# headers.net
KiCad netlist of a schematic drawn in EAGLE
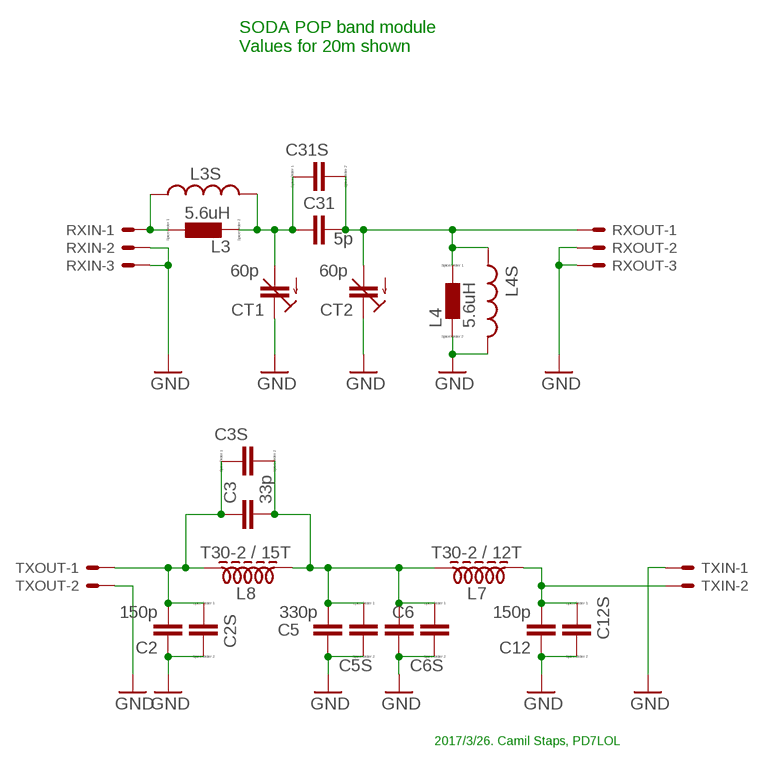
[diagram p0: schematic, sheet 1]

(export (version "E")
  (design (tool "Eeschema 10.0.6"))
  (components
    (comp (ref "C2")
      (value "150p")
      (footprint "eagle-import:C5B2.5")
      (libsource (lib "eagle-import") (part "C5/2.5"))
    )
    (comp (ref "C2S")
      (value "CC0603")
      (footprint "eagle-import:C0603")
      (libsource (lib "eagle-import") (part "CC0603"))
    )
    (comp (ref "C3")
      (value "33p")
      (footprint "eagle-import:C5B2.5")
      (libsource (lib "eagle-import") (part "C5/2.5"))
    )
    (comp (ref "C3S")
      (value "CC0603")
      (footprint "eagle-import:C0603")
      (libsource (lib "eagle-import") (part "CC0603"))
    )
    (comp (ref "C5")
      (value "330p")
      (footprint "eagle-import:C5B2.5")
      (libsource (lib "eagle-import") (part "C5/2.5"))
    )
    (comp (ref "C5S")
      (value "CC0603")
      (footprint "eagle-import:C0603")
      (libsource (lib "eagle-import") (part "CC0603"))
    )
    (comp (ref "C6")
      (value "330p")
      (footprint "eagle-import:C5B2.5")
      (libsource (lib "eagle-import") (part "C5/2.5"))
    )
    (comp (ref "C6S")
      (value "CC0603")
      (footprint "eagle-import:C0603")
      (libsource (lib "eagle-import") (part "CC0603"))
    )
    (comp (ref "C12")
      (value "150p")
      (footprint "eagle-import:C5B2.5")
      (libsource (lib "eagle-import") (part "C5/2.5"))
    )
    (comp (ref "C12S")
      (value "CC0603")
      (footprint "eagle-import:C0603")
      (libsource (lib "eagle-import") (part "CC0603"))
    )
    (comp (ref "C31")
      (value "5p")
      (footprint "eagle-import:C5B2.5")
      (libsource (lib "eagle-import") (part "C5/2.5"))
    )
    (comp (ref "C31S")
      (value "CC0603")
      (footprint "eagle-import:C0603")
      (libsource (lib "eagle-import") (part "CC0603"))
    )
    (comp (ref "CT1")
      (value "60p")
      (footprint "eagle-import:CTRIMTZ03")
      (libsource (lib "eagle-import") (part "C-TRIMMTZ03"))
    )
    (comp (ref "CT2")
      (value "60p")
      (footprint "eagle-import:CTRIMTZ03")
      (libsource (lib "eagle-import") (part "C-TRIMMTZ03"))
    )
    (comp (ref "L3")
      (value "5.6uH")
      (footprint "eagle-import:0207_10")
      (libsource (lib "eagle-import") (part "L0207/10"))
    )
    (comp (ref "L3S")
      (value "L-USL2012C")
      (footprint "eagle-import:L2012C")
      (libsource (lib "eagle-import") (part "L-USL2012C"))
    )
    (comp (ref "L4")
      (value "5.6uH")
      (footprint "eagle-import:0207_10")
      (libsource (lib "eagle-import") (part "L0207/10"))
    )
    (comp (ref "L4S")
      (value "L-USL2012C")
      (footprint "eagle-import:L2012C")
      (libsource (lib "eagle-import") (part "L-USL2012C"))
    )
    (comp (ref "L7")
      (value "T30-2 / 12T")
      (footprint "eagle-import:T30-2-28AWG-15T")
      (libsource (lib "eagle-import") (part "INDUCTORT30-2-28AWG-15T"))
    )
    (comp (ref "L8")
      (value "T30-2 / 15T")
      (footprint "eagle-import:T30-2-28AWG-15T")
      (libsource (lib "eagle-import") (part "INDUCTORT30-2-28AWG-15T"))
    )
    (comp (ref "RXIN")
      (value "22-23-2031")
      (footprint "eagle-import:22-23-2031")
      (fields (field (name "MF") "MOLEX"))
      (libsource (lib "eagle-import") (part "22-23-2031"))
    )
    (comp (ref "RXOUT")
      (value "22-23-2031")
      (footprint "eagle-import:22-23-2031")
      (fields (field (name "MF") "MOLEX"))
      (libsource (lib "eagle-import") (part "22-23-2031"))
    )
    (comp (ref "TXIN")
      (value "22-23-2021")
      (footprint "eagle-import:22-23-2021")
      (fields (field (name "MF") "MOLEX"))
      (libsource (lib "eagle-import") (part "22-23-2021"))
    )
    (comp (ref "TXOUT")
      (value "22-23-2021")
      (footprint "eagle-import:22-23-2021")
      (fields (field (name "MF") "MOLEX"))
      (libsource (lib "eagle-import") (part "22-23-2021"))
    )
  )
  (nets
    (net (code "1") (name "GND") (class "Default")
      (node (ref "C12") (pin "1") (pinfunction "1_1") (pintype "passive"))
      (node (ref "C12S") (pin "2") (pinfunction "2_2") (pintype "passive"))
      (node (ref "C2") (pin "1") (pinfunction "1_1") (pintype "passive"))
      (node (ref "C2S") (pin "2") (pinfunction "2_2") (pintype "passive"))
      (node (ref "C5") (pin "1") (pinfunction "1_1") (pintype "passive"))
      (node (ref "C5S") (pin "2") (pinfunction "2_2") (pintype "passive"))
      (node (ref "C6") (pin "1") (pinfunction "1_1") (pintype "passive"))
      (node (ref "C6S") (pin "2") (pinfunction "2_2") (pintype "passive"))
      (node (ref "CT1") (pin "1") (pinfunction "E_1") (pintype "passive"))
      (node (ref "CT2") (pin "1") (pinfunction "E_1") (pintype "passive"))
      (node (ref "L4") (pin "2") (pinfunction "2_2") (pintype "passive"))
      (node (ref "L4S") (pin "2") (pinfunction "2_2") (pintype "passive"))
      (node (ref "RXIN") (pin "2") (pinfunction "S_2") (pintype "passive"))
      (node (ref "RXIN") (pin "3") (pinfunction "S_3") (pintype "passive"))
      (node (ref "RXOUT") (pin "2") (pinfunction "S_2") (pintype "passive"))
      (node (ref "RXOUT") (pin "3") (pinfunction "S_3") (pintype "passive"))
      (node (ref "TXIN") (pin "1") (pinfunction "S_1") (pintype "passive"))
      (node (ref "TXOUT") (pin "2") (pinfunction "S_2") (pintype "passive"))
    )
    (net (code "2") (name "Net-(CT1-A)") (class "Default")
      (node (ref "C31") (pin "1") (pinfunction "1_1") (pintype "passive"))
      (node (ref "C31S") (pin "1") (pinfunction "1_1") (pintype "passive"))
      (node (ref "CT1") (pin "2") (pinfunction "A_2") (pintype "passive"))
      (node (ref "L3") (pin "2") (pinfunction "2_2") (pintype "passive"))
      (node (ref "L3S") (pin "2") (pinfunction "2_2") (pintype "passive"))
    )
    (net (code "3") (name "Net-(CT2-A)") (class "Default")
      (node (ref "C31") (pin "2") (pinfunction "2_2") (pintype "passive"))
      (node (ref "C31S") (pin "2") (pinfunction "2_2") (pintype "passive"))
      (node (ref "CT2") (pin "2") (pinfunction "A_2") (pintype "passive"))
      (node (ref "L4") (pin "1") (pinfunction "1_1") (pintype "passive"))
      (node (ref "L4S") (pin "1") (pinfunction "1_1") (pintype "passive"))
      (node (ref "RXOUT") (pin "1") (pinfunction "S_1") (pintype "passive"))
    )
    (net (code "4") (name "Net-(L7-1)") (class "Default")
      (node (ref "C12") (pin "2") (pinfunction "2_2") (pintype "passive"))
      (node (ref "C12S") (pin "1") (pinfunction "1_1") (pintype "passive"))
      (node (ref "L7") (pin "P$1") (pinfunction "1_P$1") (pintype "passive"))
      (node (ref "TXIN") (pin "2") (pinfunction "S_2") (pintype "passive"))
    )
    (net (code "5") (name "Net-(L7-2)") (class "Default")
      (node (ref "C3") (pin "2") (pinfunction "2_2") (pintype "passive"))
      (node (ref "C3S") (pin "2") (pinfunction "2_2") (pintype "passive"))
      (node (ref "C5") (pin "2") (pinfunction "2_2") (pintype "passive"))
      (node (ref "C5S") (pin "1") (pinfunction "1_1") (pintype "passive"))
      (node (ref "C6") (pin "2") (pinfunction "2_2") (pintype "passive"))
      (node (ref "C6S") (pin "1") (pinfunction "1_1") (pintype "passive"))
      (node (ref "L7") (pin "P$2") (pinfunction "2_P$2") (pintype "passive"))
      (node (ref "L8") (pin "P$1") (pinfunction "1_P$1") (pintype "passive"))
    )
    (net (code "6") (name "Net-(L8-2)") (class "Default")
      (node (ref "C2") (pin "2") (pinfunction "2_2") (pintype "passive"))
      (node (ref "C2S") (pin "1") (pinfunction "1_1") (pintype "passive"))
      (node (ref "C3") (pin "1") (pinfunction "1_1") (pintype "passive"))
      (node (ref "C3S") (pin "1") (pinfunction "1_1") (pintype "passive"))
      (node (ref "L8") (pin "P$2") (pinfunction "2_P$2") (pintype "passive"))
      (node (ref "TXOUT") (pin "1") (pinfunction "S_1") (pintype "passive"))
    )
    (net (code "7") (name "Net-(RXINA-S)") (class "Default")
      (node (ref "L3") (pin "1") (pinfunction "1_1") (pintype "passive"))
      (node (ref "L3S") (pin "1") (pinfunction "1_1") (pintype "passive"))
      (node (ref "RXIN") (pin "1") (pinfunction "S_1") (pintype "passive"))
    )
  )
)
